# HB-Dis-EP-42BW_V1_0.net
KiCad netlist of a schematic drawn in EAGLE
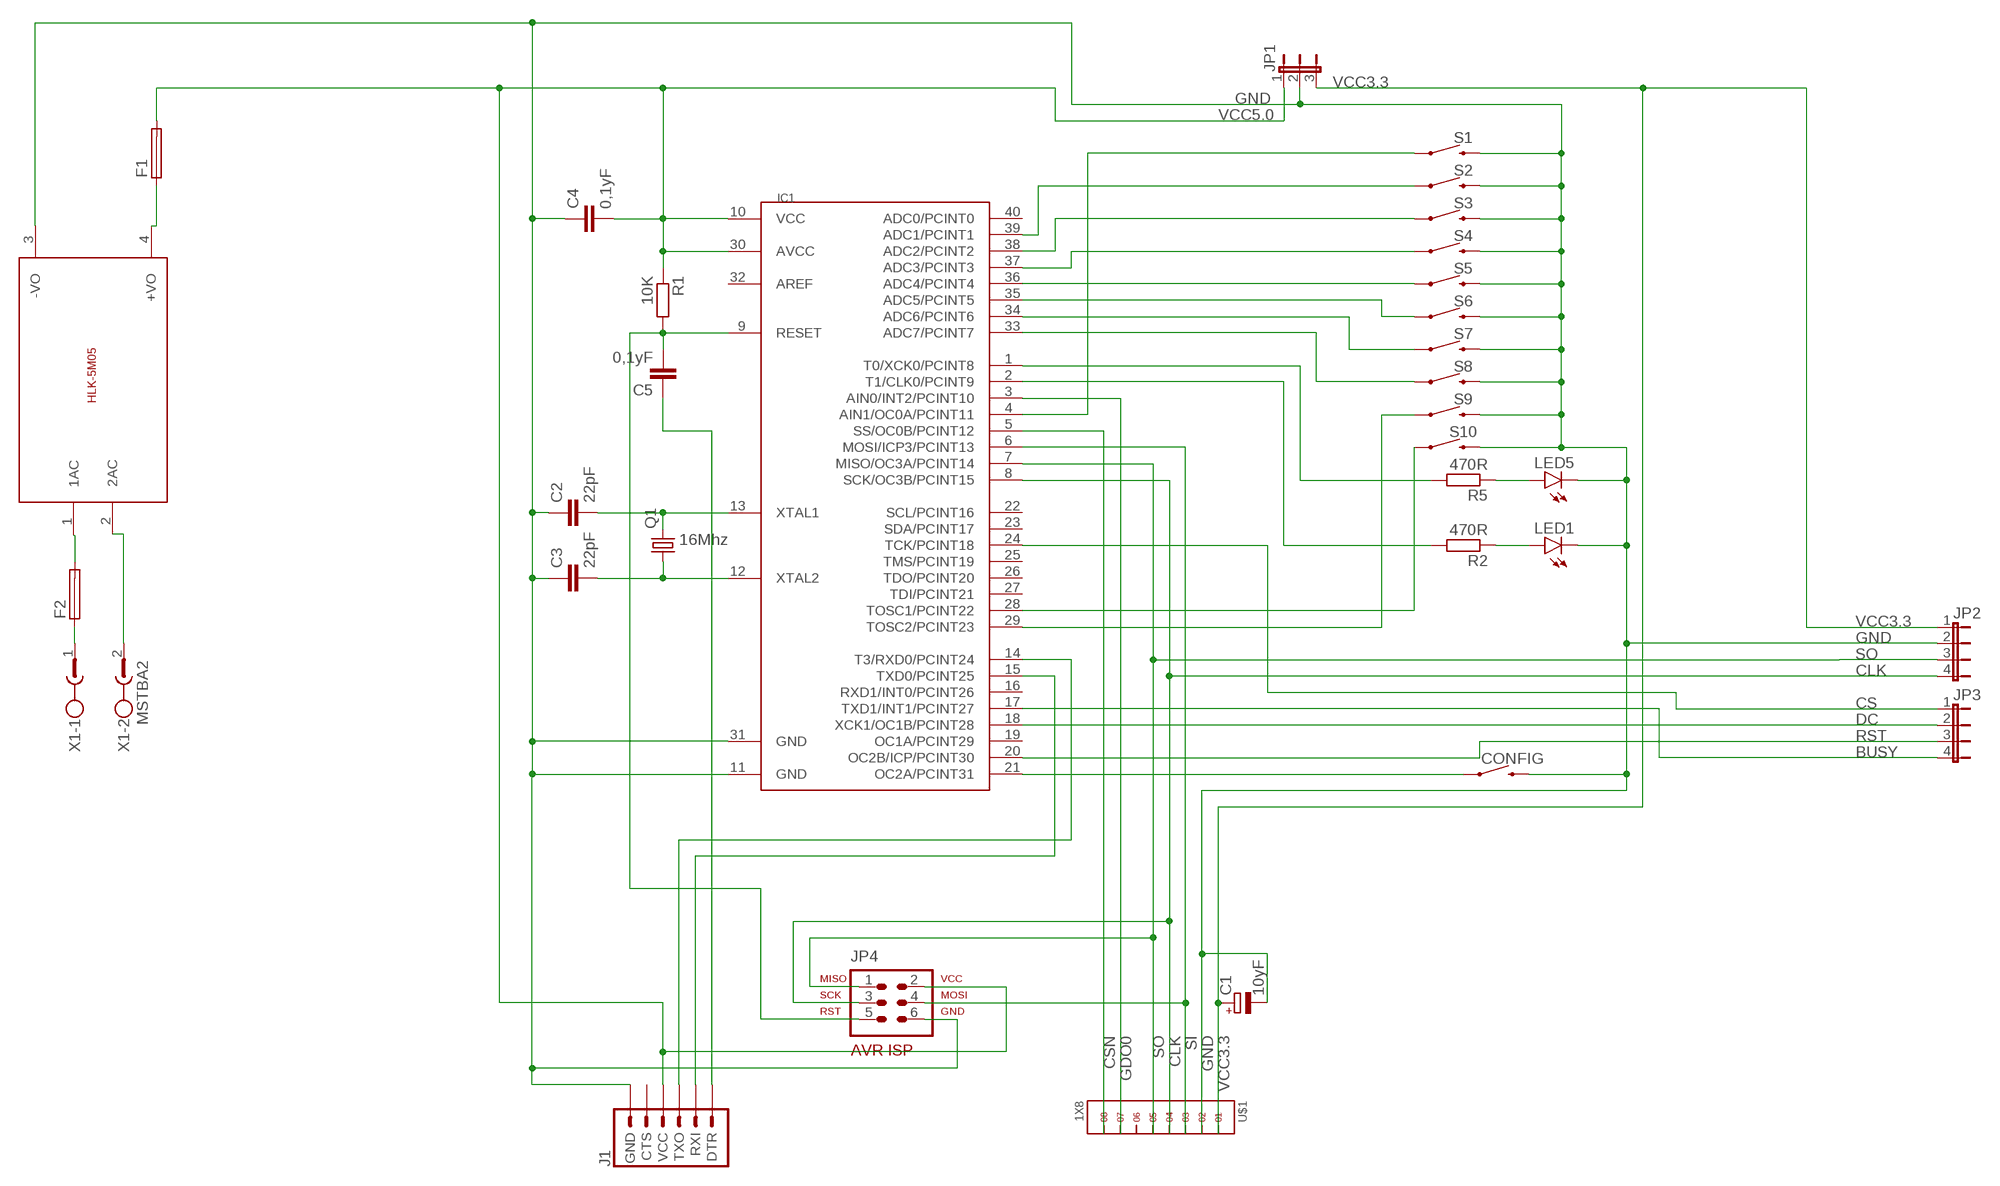
[diagram p0: schematic, sheet 1]

(export (version "E")
  (design (tool "Eeschema 10.0.6"))
  (components
    (comp (ref "C1")
      (value "10yF")
      (footprint "eagle-import:E2,5-5")
      (libsource (lib "eagle-import") (part "CPOL-EUE2.5-5"))
    )
    (comp (ref "C2")
      (value "22pF")
      (footprint "eagle-import:C025-024X044")
      (libsource (lib "eagle-import") (part "C-EU025-024X044"))
    )
    (comp (ref "C3")
      (value "22pF")
      (footprint "eagle-import:C025-024X044")
      (libsource (lib "eagle-import") (part "C-EU025-024X044"))
    )
    (comp (ref "C4")
      (value "0,1yF")
      (footprint "eagle-import:C025-024X044")
      (libsource (lib "eagle-import") (part "C-EU025-024X044"))
    )
    (comp (ref "C5")
      (value "0,1yF")
      (footprint "eagle-import:C025-024X044")
      (libsource (lib "eagle-import") (part "C-EU025-024X044"))
    )
    (comp (ref "CONFIG")
      (value "MOMENTARY-SWITCH-SPST-PTH-6.0MM-KIT")
      (footprint "eagle-import:TACTILE_SWITCH_PTH_6.0MM_KIT")
      (libsource (lib "eagle-import") (part "MOMENTARY-SWITCH-SPST-PTH-6.0MM-KIT"))
    )
    (comp (ref "F1")
      (value "SH22,5A")
      (footprint "eagle-import:SH22,5A")
      (fields (field (name "MPN") "0031.7701.11"))
      (libsource (lib "eagle-import") (part "SH22,5A"))
    )
    (comp (ref "F2")
      (value "SH22,5A")
      (footprint "eagle-import:SH22,5A")
      (fields (field (name "MPN") "0031.7701.11"))
      (libsource (lib "eagle-import") (part "SH22,5A"))
    )
    (comp (ref "IC1")
      (value "MEGA1284P")
      (footprint "eagle-import:DIL40")
      (libsource (lib "eagle-import") (part "MEGA1284P"))
    )
    (comp (ref "J1")
      (value "6_PIN_SERIAL_TARGETLONGPADS")
      (footprint "eagle-import:1X06_LONGPADS")
      (libsource (lib "eagle-import") (part "6_PIN_SERIAL_TARGETLONGPADS"))
    )
    (comp (ref "JP1")
      (value "JP2E")
      (footprint "eagle-import:JP2")
      (libsource (lib "eagle-import") (part "JP2E"))
    )
    (comp (ref "JP2")
      (value "JP4E")
      (footprint "eagle-import:JP4")
      (libsource (lib "eagle-import") (part "JP4E"))
    )
    (comp (ref "JP3")
      (value "JP4E")
      (footprint "eagle-import:JP4")
      (libsource (lib "eagle-import") (part "JP4E"))
    )
    (comp (ref "JP4")
      (value "AVR-ISP-6VERT")
      (footprint "eagle-import:AVR-ISP-6")
      (libsource (lib "eagle-import") (part "AVR-ISP-6VERT"))
    )
    (comp (ref "LED1")
      (value "LED3MM")
      (footprint "eagle-import:LED3MM")
      (libsource (lib "eagle-import") (part "LED3MM"))
    )
    (comp (ref "LED5")
      (value "LED3MM")
      (footprint "eagle-import:LED3MM")
      (libsource (lib "eagle-import") (part "LED3MM"))
    )
    (comp (ref "Q1")
      (value "16Mhz")
      (footprint "eagle-import:HC49U-V")
      (libsource (lib "eagle-import") (part "CRYSTALHC49U-V"))
    )
    (comp (ref "R1")
      (value "10K")
      (footprint "eagle-import:0309_10")
      (libsource (lib "eagle-import") (part "R-EU_0309/10"))
    )
    (comp (ref "R2")
      (value "470R")
      (footprint "eagle-import:0309_10")
      (libsource (lib "eagle-import") (part "R-EU_0309/10"))
    )
    (comp (ref "R5")
      (value "470R")
      (footprint "eagle-import:0309_10")
      (libsource (lib "eagle-import") (part "R-EU_0309/10"))
    )
    (comp (ref "S1")
      (value "MOMENTARY-SWITCH-SPST-PTH-6.0MM-KIT")
      (footprint "eagle-import:TACTILE_SWITCH_PTH_6.0MM_KIT")
      (libsource (lib "eagle-import") (part "MOMENTARY-SWITCH-SPST-PTH-6.0MM-KIT"))
    )
    (comp (ref "S2")
      (value "MOMENTARY-SWITCH-SPST-PTH-6.0MM-KIT")
      (footprint "eagle-import:TACTILE_SWITCH_PTH_6.0MM_KIT")
      (libsource (lib "eagle-import") (part "MOMENTARY-SWITCH-SPST-PTH-6.0MM-KIT"))
    )
    (comp (ref "S3")
      (value "MOMENTARY-SWITCH-SPST-PTH-6.0MM-KIT")
      (footprint "eagle-import:TACTILE_SWITCH_PTH_6.0MM_KIT")
      (libsource (lib "eagle-import") (part "MOMENTARY-SWITCH-SPST-PTH-6.0MM-KIT"))
    )
    (comp (ref "S4")
      (value "MOMENTARY-SWITCH-SPST-PTH-6.0MM-KIT")
      (footprint "eagle-import:TACTILE_SWITCH_PTH_6.0MM_KIT")
      (libsource (lib "eagle-import") (part "MOMENTARY-SWITCH-SPST-PTH-6.0MM-KIT"))
    )
    (comp (ref "S5")
      (value "MOMENTARY-SWITCH-SPST-PTH-6.0MM-KIT")
      (footprint "eagle-import:TACTILE_SWITCH_PTH_6.0MM_KIT")
      (libsource (lib "eagle-import") (part "MOMENTARY-SWITCH-SPST-PTH-6.0MM-KIT"))
    )
    (comp (ref "S6")
      (value "MOMENTARY-SWITCH-SPST-PTH-6.0MM-KIT")
      (footprint "eagle-import:TACTILE_SWITCH_PTH_6.0MM_KIT")
      (libsource (lib "eagle-import") (part "MOMENTARY-SWITCH-SPST-PTH-6.0MM-KIT"))
    )
    (comp (ref "S7")
      (value "MOMENTARY-SWITCH-SPST-PTH-6.0MM-KIT")
      (footprint "eagle-import:TACTILE_SWITCH_PTH_6.0MM_KIT")
      (libsource (lib "eagle-import") (part "MOMENTARY-SWITCH-SPST-PTH-6.0MM-KIT"))
    )
    (comp (ref "S8")
      (value "MOMENTARY-SWITCH-SPST-PTH-6.0MM-KIT")
      (footprint "eagle-import:TACTILE_SWITCH_PTH_6.0MM_KIT")
      (libsource (lib "eagle-import") (part "MOMENTARY-SWITCH-SPST-PTH-6.0MM-KIT"))
    )
    (comp (ref "S9")
      (value "MOMENTARY-SWITCH-SPST-PTH-6.0MM-KIT")
      (footprint "eagle-import:TACTILE_SWITCH_PTH_6.0MM_KIT")
      (libsource (lib "eagle-import") (part "MOMENTARY-SWITCH-SPST-PTH-6.0MM-KIT"))
    )
    (comp (ref "S10")
      (value "MOMENTARY-SWITCH-SPST-PTH-6.0MM-KIT")
      (footprint "eagle-import:TACTILE_SWITCH_PTH_6.0MM_KIT")
      (libsource (lib "eagle-import") (part "MOMENTARY-SWITCH-SPST-PTH-6.0MM-KIT"))
    )
    (comp (ref "U$1")
      (value "1X8")
      (footprint "eagle-import:1X8")
      (libsource (lib "eagle-import") (part "1X8"))
    )
    (comp (ref "U$3")
      (value "5VDC/5W")
      (footprint "eagle-import:HLK-5M05")
      (libsource (lib "eagle-import") (part "HLK-5M05"))
    )
    (comp (ref "X1")
      (value "MSTBA2")
      (footprint "eagle-import:MSTBA2")
      (fields (field (name "MF") "FARNELL") (field (name "MPN") "1757242"))
      (libsource (lib "eagle-import") (part "MSTBA2"))
    )
  )
  (nets
    (net (code "1") (name "/BUSY") (class "Default")
      (node (ref "IC1") (pin "17") (pinfunction "TXD1/INT1/PCINT27_17") (pintype "bidirectional"))
      (node (ref "JP3") (pin "4") (pinfunction "4_4") (pintype "passive"))
    )
    (net (code "2") (name "/CLK") (class "Default")
      (node (ref "IC1") (pin "8") (pinfunction "SCK/OC3B/PCINT15_8") (pintype "bidirectional"))
      (node (ref "JP2") (pin "4") (pinfunction "4_4") (pintype "passive"))
      (node (ref "JP4") (pin "3") (pinfunction "3_3") (pintype "passive"))
      (node (ref "U$1") (pin "4") (pinfunction "4_4") (pintype "bidirectional"))
    )
    (net (code "3") (name "/CS") (class "Default")
      (node (ref "IC1") (pin "24") (pinfunction "TCK/PCINT18_24") (pintype "bidirectional"))
      (node (ref "JP3") (pin "1") (pinfunction "1_1") (pintype "passive"))
    )
    (net (code "4") (name "/CSN") (class "Default")
      (node (ref "IC1") (pin "5") (pinfunction "SS/OC0B/PCINT12_5") (pintype "bidirectional"))
      (node (ref "U$1") (pin "8") (pinfunction "8_8") (pintype "bidirectional"))
    )
    (net (code "5") (name "/DC") (class "Default")
      (node (ref "IC1") (pin "18") (pinfunction "XCK1/OC1B/PCINT28_18") (pintype "bidirectional"))
      (node (ref "JP3") (pin "2") (pinfunction "2_2") (pintype "passive"))
    )
    (net (code "6") (name "/GDO0") (class "Default")
      (node (ref "IC1") (pin "3") (pinfunction "AIN0/INT2/PCINT10_3") (pintype "bidirectional"))
      (node (ref "U$1") (pin "7") (pinfunction "7_7") (pintype "bidirectional"))
    )
    (net (code "7") (name "/GND") (class "Default")
      (node (ref "C1") (pin "-") (pinfunction "-_-") (pintype "passive"))
      (node (ref "C2") (pin "1") (pinfunction "1_1") (pintype "passive"))
      (node (ref "C3") (pin "1") (pinfunction "1_1") (pintype "passive"))
      (node (ref "C4") (pin "1") (pinfunction "1_1") (pintype "passive"))
      (node (ref "CONFIG") (pin "3") (pinfunction "2_3") (pintype "passive"))
      (node (ref "IC1") (pin "11") (pinfunction "GND_11") (pintype "bidirectional"))
      (node (ref "IC1") (pin "31") (pinfunction "GND_31") (pintype "bidirectional"))
      (node (ref "J1") (pin "6") (pinfunction "GND_6") (pintype "passive"))
      (node (ref "JP1") (pin "2") (pinfunction "2_2") (pintype "passive"))
      (node (ref "JP2") (pin "2") (pinfunction "2_2") (pintype "passive"))
      (node (ref "JP4") (pin "6") (pinfunction "6_6") (pintype "passive"))
      (node (ref "LED1") (pin "K") (pinfunction "C_K") (pintype "passive"))
      (node (ref "LED5") (pin "K") (pinfunction "C_K") (pintype "passive"))
      (node (ref "S1") (pin "3") (pinfunction "2_3") (pintype "passive"))
      (node (ref "S10") (pin "3") (pinfunction "2_3") (pintype "passive"))
      (node (ref "S2") (pin "3") (pinfunction "2_3") (pintype "passive"))
      (node (ref "S3") (pin "3") (pinfunction "2_3") (pintype "passive"))
      (node (ref "S4") (pin "3") (pinfunction "2_3") (pintype "passive"))
      (node (ref "S5") (pin "3") (pinfunction "2_3") (pintype "passive"))
      (node (ref "S6") (pin "3") (pinfunction "2_3") (pintype "passive"))
      (node (ref "S7") (pin "3") (pinfunction "2_3") (pintype "passive"))
      (node (ref "S8") (pin "3") (pinfunction "2_3") (pintype "passive"))
      (node (ref "S9") (pin "3") (pinfunction "2_3") (pintype "passive"))
      (node (ref "U$1") (pin "2") (pinfunction "2_2") (pintype "bidirectional"))
      (node (ref "U$3") (pin "3") (pinfunction "-VO_3") (pintype "bidirectional"))
    )
    (net (code "8") (name "/RST") (class "Default")
      (node (ref "IC1") (pin "20") (pinfunction "OC2B/ICP/PCINT30_20") (pintype "bidirectional"))
      (node (ref "JP3") (pin "3") (pinfunction "3_3") (pintype "passive"))
    )
    (net (code "9") (name "/SI") (class "Default")
      (node (ref "IC1") (pin "6") (pinfunction "MOSI/ICP3/PCINT13_6") (pintype "bidirectional"))
      (node (ref "JP4") (pin "4") (pinfunction "4_4") (pintype "passive"))
      (node (ref "U$1") (pin "3") (pinfunction "3_3") (pintype "bidirectional"))
    )
    (net (code "10") (name "/SO") (class "Default")
      (node (ref "IC1") (pin "7") (pinfunction "MISO/OC3A/PCINT14_7") (pintype "bidirectional"))
      (node (ref "JP2") (pin "3") (pinfunction "3_3") (pintype "passive"))
      (node (ref "JP4") (pin "1") (pinfunction "1_1") (pintype "passive"))
      (node (ref "U$1") (pin "5") (pinfunction "5_5") (pintype "bidirectional"))
    )
    (net (code "11") (name "/VCC3.3") (class "Default")
      (node (ref "C1") (pin "+") (pinfunction "+_+") (pintype "passive"))
      (node (ref "JP1") (pin "3") (pinfunction "3_3") (pintype "passive"))
      (node (ref "JP2") (pin "1") (pinfunction "1_1") (pintype "passive"))
      (node (ref "U$1") (pin "1") (pinfunction "1_1") (pintype "bidirectional"))
    )
    (net (code "12") (name "/VCC5.0") (class "Default")
      (node (ref "C4") (pin "2") (pinfunction "2_2") (pintype "passive"))
      (node (ref "F1") (pin "2") (pinfunction "2_2") (pintype "passive"))
      (node (ref "IC1") (pin "10") (pinfunction "VCC_10") (pintype "bidirectional"))
      (node (ref "IC1") (pin "30") (pinfunction "AVCC_30") (pintype "bidirectional"))
      (node (ref "J1") (pin "4") (pinfunction "VCC_4") (pintype "passive"))
      (node (ref "JP1") (pin "1") (pinfunction "1_1") (pintype "passive"))
      (node (ref "JP4") (pin "2") (pinfunction "2_2") (pintype "passive"))
      (node (ref "R1") (pin "1") (pinfunction "1_1") (pintype "passive"))
    )
    (net (code "13") (name "Net-(F2-Pad1)") (class "Default")
      (node (ref "F2") (pin "1") (pinfunction "1_1") (pintype "passive"))
      (node (ref "X1") (pin "1") (pinfunction "1_1") (pintype "passive"))
    )
    (net (code "14") (name "Net-(IC1-ADC1{slash}PCINT1)") (class "Default")
      (node (ref "IC1") (pin "39") (pinfunction "ADC1/PCINT1_39") (pintype "bidirectional"))
      (node (ref "S2") (pin "1") (pinfunction "1_1") (pintype "passive"))
    )
    (net (code "15") (name "Net-(IC1-ADC2{slash}PCINT2)") (class "Default")
      (node (ref "IC1") (pin "38") (pinfunction "ADC2/PCINT2_38") (pintype "bidirectional"))
      (node (ref "S3") (pin "1") (pinfunction "1_1") (pintype "passive"))
    )
    (net (code "16") (name "Net-(IC1-ADC3{slash}PCINT3)") (class "Default")
      (node (ref "IC1") (pin "37") (pinfunction "ADC3/PCINT3_37") (pintype "bidirectional"))
      (node (ref "S4") (pin "1") (pinfunction "1_1") (pintype "passive"))
    )
    (net (code "17") (name "Net-(IC1-ADC4{slash}PCINT4)") (class "Default")
      (node (ref "IC1") (pin "36") (pinfunction "ADC4/PCINT4_36") (pintype "bidirectional"))
      (node (ref "S5") (pin "1") (pinfunction "1_1") (pintype "passive"))
    )
    (net (code "18") (name "Net-(IC1-ADC5{slash}PCINT5)") (class "Default")
      (node (ref "IC1") (pin "35") (pinfunction "ADC5/PCINT5_35") (pintype "bidirectional"))
      (node (ref "S6") (pin "1") (pinfunction "1_1") (pintype "passive"))
    )
    (net (code "19") (name "Net-(IC1-ADC6{slash}PCINT6)") (class "Default")
      (node (ref "IC1") (pin "34") (pinfunction "ADC6/PCINT6_34") (pintype "bidirectional"))
      (node (ref "S7") (pin "1") (pinfunction "1_1") (pintype "passive"))
    )
    (net (code "20") (name "Net-(IC1-ADC7{slash}PCINT7)") (class "Default")
      (node (ref "IC1") (pin "33") (pinfunction "ADC7/PCINT7_33") (pintype "bidirectional"))
      (node (ref "S8") (pin "1") (pinfunction "1_1") (pintype "passive"))
    )
    (net (code "21") (name "Net-(IC1-AIN1{slash}OC0A{slash}PCINT11)") (class "Default")
      (node (ref "IC1") (pin "4") (pinfunction "AIN1/OC0A/PCINT11_4") (pintype "bidirectional"))
      (node (ref "S1") (pin "1") (pinfunction "1_1") (pintype "passive"))
    )
    (net (code "22") (name "Net-(IC1-OC2A{slash}PCINT31)") (class "Default")
      (node (ref "CONFIG") (pin "1") (pinfunction "1_1") (pintype "passive"))
      (node (ref "IC1") (pin "21") (pinfunction "OC2A/PCINT31_21") (pintype "bidirectional"))
    )
    (net (code "23") (name "Net-(IC1-RESET)") (class "Default")
      (node (ref "C5") (pin "2") (pinfunction "2_2") (pintype "passive"))
      (node (ref "IC1") (pin "9") (pinfunction "RESET_9") (pintype "bidirectional"))
      (node (ref "JP4") (pin "5") (pinfunction "5_5") (pintype "passive"))
      (node (ref "R1") (pin "2") (pinfunction "2_2") (pintype "passive"))
    )
    (net (code "24") (name "Net-(IC1-T0{slash}XCK0{slash}PCINT8)") (class "Default")
      (node (ref "IC1") (pin "1") (pinfunction "T0/XCK0/PCINT8_1") (pintype "bidirectional"))
      (node (ref "R5") (pin "2") (pinfunction "2_2") (pintype "passive"))
    )
    (net (code "25") (name "Net-(IC1-T1{slash}CLK0{slash}PCINT9)") (class "Default")
      (node (ref "IC1") (pin "2") (pinfunction "T1/CLK0/PCINT9_2") (pintype "bidirectional"))
      (node (ref "R2") (pin "2") (pinfunction "2_2") (pintype "passive"))
    )
    (net (code "26") (name "Net-(IC1-T3{slash}RXD0{slash}PCINT24)") (class "Default")
      (node (ref "IC1") (pin "14") (pinfunction "T3/RXD0/PCINT24_14") (pintype "bidirectional"))
      (node (ref "J1") (pin "3") (pinfunction "TXO_3") (pintype "passive"))
    )
    (net (code "27") (name "Net-(IC1-TOSC1{slash}PCINT22)") (class "Default")
      (node (ref "IC1") (pin "28") (pinfunction "TOSC1/PCINT22_28") (pintype "bidirectional"))
      (node (ref "S10") (pin "1") (pinfunction "1_1") (pintype "passive"))
    )
    (net (code "28") (name "Net-(IC1-TOSC2{slash}PCINT23)") (class "Default")
      (node (ref "IC1") (pin "29") (pinfunction "TOSC2/PCINT23_29") (pintype "bidirectional"))
      (node (ref "S9") (pin "1") (pinfunction "1_1") (pintype "passive"))
    )
    (net (code "29") (name "Net-(IC1-TXD0{slash}PCINT25)") (class "Default")
      (node (ref "IC1") (pin "15") (pinfunction "TXD0/PCINT25_15") (pintype "bidirectional"))
      (node (ref "J1") (pin "2") (pinfunction "RXI_2") (pintype "passive"))
    )
    (net (code "30") (name "Net-(IC1-XTAL1)") (class "Default")
      (node (ref "C2") (pin "2") (pinfunction "2_2") (pintype "passive"))
      (node (ref "IC1") (pin "13") (pinfunction "XTAL1_13") (pintype "bidirectional"))
      (node (ref "Q1") (pin "2") (pinfunction "2_2") (pintype "passive"))
    )
    (net (code "31") (name "Net-(IC1-XTAL2)") (class "Default")
      (node (ref "C3") (pin "2") (pinfunction "2_2") (pintype "passive"))
      (node (ref "IC1") (pin "12") (pinfunction "XTAL2_12") (pintype "bidirectional"))
      (node (ref "Q1") (pin "1") (pinfunction "1_1") (pintype "passive"))
    )
    (net (code "32") (name "Net-(J1-DTR)") (class "Default")
      (node (ref "C5") (pin "1") (pinfunction "1_1") (pintype "passive"))
      (node (ref "J1") (pin "1") (pinfunction "DTR_1") (pintype "passive"))
    )
    (net (code "33") (name "Net-(LED1-PadA)") (class "Default")
      (node (ref "LED1") (pin "A") (pinfunction "A_A") (pintype "passive"))
      (node (ref "R2") (pin "1") (pinfunction "1_1") (pintype "passive"))
    )
    (net (code "34") (name "Net-(LED5-PadA)") (class "Default")
      (node (ref "LED5") (pin "A") (pinfunction "A_A") (pintype "passive"))
      (node (ref "R5") (pin "1") (pinfunction "1_1") (pintype "passive"))
    )
    (net (code "35") (name "Net-(U$3-+VO)") (class "Default")
      (node (ref "F1") (pin "1") (pinfunction "1_1") (pintype "passive"))
      (node (ref "U$3") (pin "4") (pinfunction "+VO_4") (pintype "bidirectional"))
    )
    (net (code "36") (name "Net-(U$3-1AC)") (class "Default")
      (node (ref "F2") (pin "2") (pinfunction "2_2") (pintype "passive"))
      (node (ref "U$3") (pin "1") (pinfunction "1AC_1") (pintype "bidirectional"))
    )
    (net (code "37") (name "Net-(U$3-2AC)") (class "Default")
      (node (ref "U$3") (pin "2") (pinfunction "2AC_2") (pintype "bidirectional"))
      (node (ref "X1") (pin "2") (pinfunction "1_2") (pintype "passive"))
    )
    (net (code "38") (name "unconnected-(IC1-ADC0{slash}PCINT0-Pad40)") (class "Default")
      (node (ref "IC1") (pin "40") (pinfunction "ADC0/PCINT0_40") (pintype "bidirectional"))
    )
    (net (code "39") (name "unconnected-(IC1-AREF-Pad32)") (class "Default")
      (node (ref "IC1") (pin "32") (pinfunction "AREF_32") (pintype "bidirectional"))
    )
    (net (code "40") (name "unconnected-(IC1-OC1A{slash}PCINT29-Pad19)") (class "Default")
      (node (ref "IC1") (pin "19") (pinfunction "OC1A/PCINT29_19") (pintype "bidirectional"))
    )
    (net (code "41") (name "unconnected-(IC1-RXD1{slash}INT0{slash}PCINT26-Pad16)") (class "Default")
      (node (ref "IC1") (pin "16") (pinfunction "RXD1/INT0/PCINT26_16") (pintype "bidirectional"))
    )
    (net (code "42") (name "unconnected-(IC1-SCL{slash}PCINT16-Pad22)") (class "Default")
      (node (ref "IC1") (pin "22") (pinfunction "SCL/PCINT16_22") (pintype "bidirectional"))
    )
    (net (code "43") (name "unconnected-(IC1-SDA{slash}PCINT17-Pad23)") (class "Default")
      (node (ref "IC1") (pin "23") (pinfunction "SDA/PCINT17_23") (pintype "bidirectional"))
    )
    (net (code "44") (name "unconnected-(IC1-TDI{slash}PCINT21-Pad27)") (class "Default")
      (node (ref "IC1") (pin "27") (pinfunction "TDI/PCINT21_27") (pintype "bidirectional"))
    )
    (net (code "45") (name "unconnected-(IC1-TDO{slash}PCINT20-Pad26)") (class "Default")
      (node (ref "IC1") (pin "26") (pinfunction "TDO/PCINT20_26") (pintype "bidirectional"))
    )
    (net (code "46") (name "unconnected-(IC1-TMS{slash}PCINT19-Pad25)") (class "Default")
      (node (ref "IC1") (pin "25") (pinfunction "TMS/PCINT19_25") (pintype "bidirectional"))
    )
    (net (code "47") (name "unconnected-(J1-CTS-Pad5)") (class "Default")
      (node (ref "J1") (pin "5") (pinfunction "CTS_5") (pintype "passive"))
    )
    (net (code "48") (name "unconnected-(U$1-Pad6)") (class "Default")
      (node (ref "U$1") (pin "6") (pinfunction "6_6") (pintype "bidirectional"))
    )
  )
)
